# LCD.net
KiCad netlist of a schematic drawn in Altium Designer
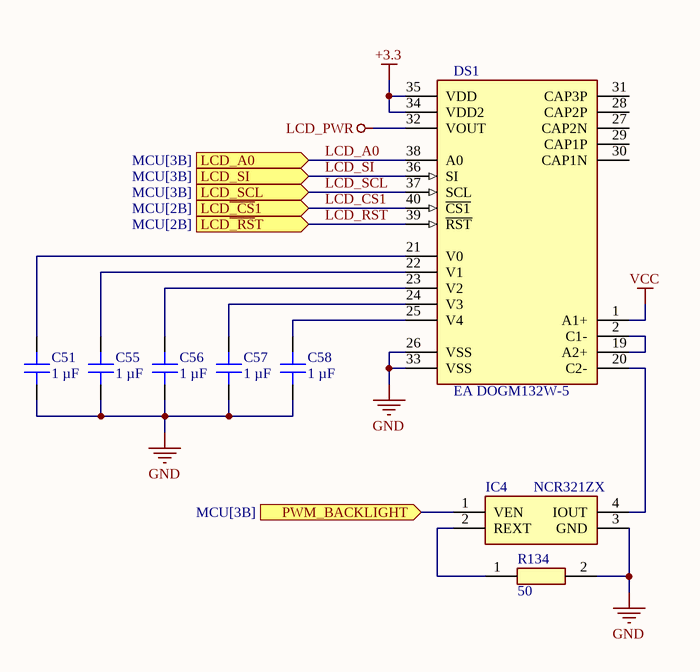
[diagram p0: LCD.SchDoc]

(export (version "E")
  (design (tool "Eeschema 10.0.6"))
  (components
    (comp (ref "C51")
      (value "1 µF")
      (footprint "CAP 1206_3216 - 0.8MM")
      (description "CAP CER 1UF 50V X7R 1206")
      (fields
        (field (name "PART NUMBER") "885012208093")
        (field (name "CAPACITANCE") "1 µF")
        (field (name "MANUFACTURER") "Würth Elektronik")
      )
      (libsource (lib "Celestial Altium Library - altium_library") (part "Capacitor"))
    )
    (comp (ref "C55")
      (value "1 µF")
      (footprint "CAP 1206_3216 - 0.8MM")
      (description "CAP CER 1UF 50V X7R 1206")
      (fields
        (field (name "PART NUMBER") "885012208093")
        (field (name "CAPACITANCE") "1 µF")
        (field (name "MANUFACTURER") "Würth Elektronik")
      )
      (libsource (lib "Celestial Altium Library - altium_library") (part "Capacitor"))
    )
    (comp (ref "C56")
      (value "1 µF")
      (footprint "CAP 1206_3216 - 0.8MM")
      (description "CAP CER 1UF 50V X7R 1206")
      (fields
        (field (name "PART NUMBER") "885012208093")
        (field (name "CAPACITANCE") "1 µF")
        (field (name "MANUFACTURER") "Würth Elektronik")
      )
      (libsource (lib "Celestial Altium Library - altium_library") (part "Capacitor"))
    )
    (comp (ref "C57")
      (value "1 µF")
      (footprint "CAP 1206_3216 - 0.8MM")
      (description "CAP CER 1UF 50V X7R 1206")
      (fields
        (field (name "PART NUMBER") "885012208093")
        (field (name "CAPACITANCE") "1 µF")
        (field (name "MANUFACTURER") "Würth Elektronik")
      )
      (libsource (lib "Celestial Altium Library - altium_library") (part "Capacitor"))
    )
    (comp (ref "C58")
      (value "1 µF")
      (footprint "CAP 1206_3216 - 0.8MM")
      (description "CAP CER 1UF 50V X7R 1206")
      (fields
        (field (name "PART NUMBER") "885012208093")
        (field (name "CAPACITANCE") "1 µF")
        (field (name "MANUFACTURER") "Würth Elektronik")
      )
      (libsource (lib "Celestial Altium Library - altium_library") (part "Capacitor"))
    )
    (comp (ref "DS1")
      (value "EA DOGM132W-5")
      (footprint "FP-EA_DOGM132L-5-MFG")
      (description "LCD MOD GRAPH 132X32 Y/G")
      (libsource (lib "za_koncar") (part "CMP-137185-000001-1"))
    )
    (comp (ref "IC4")
      (value "NCR321ZX")
      (footprint "SOT230P700X180-4N")
      (description "Integrated Circuit")
      (fields (field (name "MOUSER PART NUMBER") "771-NCR321ZX"))
      (libsource (lib "za_koncar") (part "NCR321ZX"))
    )
    (comp (ref "R134")
      (value "50")
      (footprint "RESC6332X65N")
      (description "Resistor")
      (fields (field (name "MANUFACTURER_PART_NUMBER") "RNCL2512FT50R0"))
      (libsource (lib "za_koncar") (part "RNCL2512FT50R0"))
    )
  )
  (nets
    (net (code "1") (name "+3.3") (class "Default")
      (node (ref "DS1") (pin "34") (pinfunction "VDD2_34") (pintype "power_in"))
      (node (ref "DS1") (pin "35") (pinfunction "VDD_35") (pintype "power_in"))
    )
    (net (code "2") (name "/LCD_A0") (class "Default")
      (node (ref "DS1") (pin "38") (pinfunction "A0_38") (pintype "passive"))
    )
    (net (code "3") (name "/LCD_SCL") (class "Default")
      (node (ref "DS1") (pin "37") (pinfunction "SCL_37") (pintype "input"))
    )
    (net (code "4") (name "/LCD_SI") (class "Default")
      (node (ref "DS1") (pin "36") (pinfunction "SI_36") (pintype "input"))
    )
    (net (code "5") (name "/LCD~{_CS}1") (class "Default")
      (node (ref "DS1") (pin "40") (pinfunction "~{CS1}_40") (pintype "input"))
    )
    (net (code "6") (name "/LCD~{_RS}T") (class "Default")
      (node (ref "DS1") (pin "39") (pinfunction "~{RST}_39") (pintype "input"))
    )
    (net (code "7") (name "/PWM_BACKLIGHT") (class "Default")
      (node (ref "IC4") (pin "1") (pinfunction "VEN_1") (pintype "passive"))
    )
    (net (code "8") (name "GND") (class "Default")
      (node (ref "C51") (pin "1") (pinfunction "1_1") (pintype "passive"))
      (node (ref "C55") (pin "1") (pinfunction "1_1") (pintype "passive"))
      (node (ref "C56") (pin "1") (pinfunction "1_1") (pintype "passive"))
      (node (ref "C57") (pin "1") (pinfunction "1_1") (pintype "passive"))
      (node (ref "C58") (pin "1") (pinfunction "1_1") (pintype "passive"))
      (node (ref "DS1") (pin "26") (pinfunction "VSS_26") (pintype "power_in"))
      (node (ref "DS1") (pin "33") (pinfunction "VSS_33") (pintype "power_in"))
      (node (ref "IC4") (pin "3") (pinfunction "GND_3") (pintype "passive"))
      (node (ref "R134") (pin "2") (pinfunction "2_2") (pintype "passive"))
    )
    (net (code "9") (name "LCD_PWR") (class "Default")
      (node (ref "DS1") (pin "32") (pinfunction "VOUT_32") (pintype "power_in"))
    )
    (net (code "10") (name "Net-(DS1-A2+)") (class "Default")
      (node (ref "DS1") (pin "19") (pinfunction "A2+_19") (pintype "passive"))
      (node (ref "DS1") (pin "2") (pinfunction "C1-_2") (pintype "passive"))
    )
    (net (code "11") (name "Net-(DS1-C2-)") (class "Default")
      (node (ref "DS1") (pin "20") (pinfunction "C2-_20") (pintype "passive"))
      (node (ref "IC4") (pin "4") (pinfunction "IOUT_4") (pintype "passive"))
    )
    (net (code "12") (name "Net-(DS1-V0)") (class "Default")
      (node (ref "C51") (pin "2") (pinfunction "2_2") (pintype "passive"))
      (node (ref "DS1") (pin "21") (pinfunction "V0_21") (pintype "passive"))
    )
    (net (code "13") (name "Net-(DS1-V1)") (class "Default")
      (node (ref "C55") (pin "2") (pinfunction "2_2") (pintype "passive"))
      (node (ref "DS1") (pin "22") (pinfunction "V1_22") (pintype "passive"))
    )
    (net (code "14") (name "Net-(DS1-V2)") (class "Default")
      (node (ref "C56") (pin "2") (pinfunction "2_2") (pintype "passive"))
      (node (ref "DS1") (pin "23") (pinfunction "V2_23") (pintype "passive"))
    )
    (net (code "15") (name "Net-(DS1-V3)") (class "Default")
      (node (ref "C57") (pin "2") (pinfunction "2_2") (pintype "passive"))
      (node (ref "DS1") (pin "24") (pinfunction "V3_24") (pintype "passive"))
    )
    (net (code "16") (name "Net-(DS1-V4)") (class "Default")
      (node (ref "C58") (pin "2") (pinfunction "2_2") (pintype "passive"))
      (node (ref "DS1") (pin "25") (pinfunction "V4_25") (pintype "passive"))
    )
    (net (code "17") (name "Net-(IC4-REXT)") (class "Default")
      (node (ref "IC4") (pin "2") (pinfunction "REXT_2") (pintype "passive"))
      (node (ref "R134") (pin "1") (pinfunction "1_1") (pintype "passive"))
    )
    (net (code "18") (name "VCC") (class "Default")
      (node (ref "DS1") (pin "1") (pinfunction "A1+_1") (pintype "passive"))
    )
    (net (code "19") (name "unconnected-(DS1-CAP1N-Pad30)") (class "Default")
      (node (ref "DS1") (pin "30") (pinfunction "CAP1N_30") (pintype "passive"))
    )
    (net (code "20") (name "unconnected-(DS1-CAP1P-Pad29)") (class "Default")
      (node (ref "DS1") (pin "29") (pinfunction "CAP1P_29") (pintype "passive"))
    )
    (net (code "21") (name "unconnected-(DS1-CAP2N-Pad27)") (class "Default")
      (node (ref "DS1") (pin "27") (pinfunction "CAP2N_27") (pintype "passive"))
    )
    (net (code "22") (name "unconnected-(DS1-CAP2P-Pad28)") (class "Default")
      (node (ref "DS1") (pin "28") (pinfunction "CAP2P_28") (pintype "passive"))
    )
    (net (code "23") (name "unconnected-(DS1-CAP3P-Pad31)") (class "Default")
      (node (ref "DS1") (pin "31") (pinfunction "CAP3P_31") (pintype "passive"))
    )
  )
)
